# Buck_Boost.net
KiCad netlist of a schematic drawn in Altium Designer
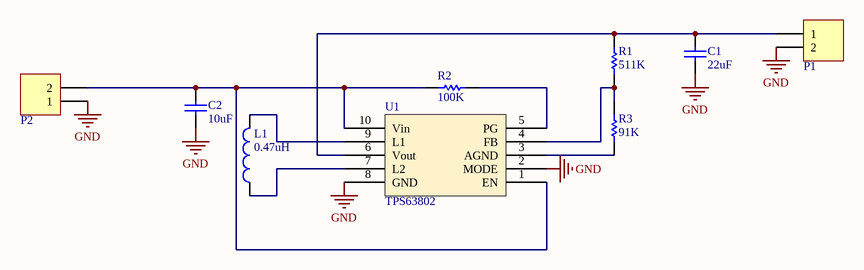
[diagram p0: Buck_Boost.SchDoc]

(export (version "E")
  (design (tool "Eeschema 10.0.6"))
  (components
    (comp (ref "C1")
      (value "22uF")
      (footprint "CAP-SM-0603")
      (description "Capacitor")
      (fields (field (name "Comment") "Cap Non-Pol SMD"))
      (libsource (lib "PIF_Library") (part "Cap Non-Pol SMD"))
    )
    (comp (ref "C2")
      (value "10uF")
      (footprint "CAP-SM-0603")
      (description "Capacitor")
      (fields (field (name "Comment") "Cap Non-Pol SMD"))
      (libsource (lib "PIF_Library") (part "Cap Non-Pol SMD"))
    )
    (comp (ref "L1")
      (value "0.47uH")
      (footprint "INDUCTOR 12.5x12.5")
      (description "Inductor")
      (libsource (lib "PIF_Library") (part "Inductor"))
    )
    (comp (ref "P1")
      (value "Domino 2")
      (footprint "DOMINO 2- 5mm")
      (description "Domino, 2-Pin")
      (fields (field (name "PUBLISHER") "Altium Limited"))
      (libsource (lib "") (part "Domino 2_1"))
    )
    (comp (ref "P2")
      (value "Domino 2")
      (footprint "DOMINO 2- 5mm")
      (description "Domino, 2-Pin")
      (fields (field (name "PUBLISHER") "Altium Limited"))
      (libsource (lib "PIF_Library") (part "Domino 2"))
    )
    (comp (ref "R1")
      (value "511K")
      (footprint "RES-SM-0603")
      (description "Resistor")
      (fields (field (name "Comment") "RESISTOR SMD"))
      (libsource (lib "PIF_Library") (part "RESISTOR SMD"))
    )
    (comp (ref "R2")
      (value "100K")
      (footprint "RES-SM-0603")
      (description "Resistor")
      (fields (field (name "Comment") "RESISTOR SMD"))
      (libsource (lib "PIF_Library") (part "RESISTOR SMD"))
    )
    (comp (ref "R3")
      (value "91K")
      (footprint "RES-SM-0603")
      (description "Resistor")
      (fields (field (name "Comment") "RESISTOR SMD"))
      (libsource (lib "PIF_Library") (part "RESISTOR SMD"))
    )
    (comp (ref "U1")
      (value "TPS63802")
      (footprint "TPS63802")
      (description "SMD")
      (libsource (lib "buck_boost") (part "TPS63802"))
    )
  )
  (nets
    (net (code "1") (name "GND") (class "Default")
      (node (ref "C1") (pin "2") (pinfunction "2_2") (pintype "passive"))
      (node (ref "C2") (pin "2") (pinfunction "2_2") (pintype "passive"))
      (node (ref "P1") (pin "2") (pinfunction "2_2") (pintype "passive"))
      (node (ref "P2") (pin "1") (pinfunction "1_1") (pintype "passive"))
      (node (ref "U1") (pin "2") (pinfunction "MODE_2") (pintype "passive"))
      (node (ref "U1") (pin "8") (pinfunction "GND_8") (pintype "passive"))
    )
    (net (code "2") (name "Net-(U1-AGND)") (class "Default")
      (node (ref "R3") (pin "1") (pinfunction "1_1") (pintype "passive"))
      (node (ref "U1") (pin "3") (pinfunction "AGND_3") (pintype "passive"))
    )
    (net (code "3") (name "Net-(U1-EN)") (class "Default")
      (node (ref "C2") (pin "1") (pinfunction "1_1") (pintype "passive"))
      (node (ref "P2") (pin "2") (pinfunction "2_2") (pintype "passive"))
      (node (ref "R2") (pin "1") (pinfunction "1_1") (pintype "passive"))
      (node (ref "U1") (pin "1") (pinfunction "EN_1") (pintype "passive"))
      (node (ref "U1") (pin "10") (pinfunction "Vin_10") (pintype "passive"))
    )
    (net (code "4") (name "Net-(U1-FB)") (class "Default")
      (node (ref "R1") (pin "1") (pinfunction "1_1") (pintype "passive"))
      (node (ref "R3") (pin "2") (pinfunction "2_2") (pintype "passive"))
      (node (ref "U1") (pin "4") (pinfunction "FB_4") (pintype "passive"))
    )
    (net (code "5") (name "Net-(U1-L1)") (class "Default")
      (node (ref "L1") (pin "2") (pinfunction "2_2") (pintype "passive"))
      (node (ref "U1") (pin "9") (pinfunction "L1_9") (pintype "passive"))
    )
    (net (code "6") (name "Net-(U1-L2)") (class "Default")
      (node (ref "L1") (pin "1") (pinfunction "1_1") (pintype "passive"))
      (node (ref "U1") (pin "7") (pinfunction "L2_7") (pintype "passive"))
    )
    (net (code "7") (name "Net-(U1-PG)") (class "Default")
      (node (ref "R2") (pin "2") (pinfunction "2_2") (pintype "passive"))
      (node (ref "U1") (pin "5") (pinfunction "PG_5") (pintype "passive"))
    )
    (net (code "8") (name "Net-(U1-Vout)") (class "Default")
      (node (ref "C1") (pin "1") (pinfunction "1_1") (pintype "passive"))
      (node (ref "P1") (pin "1") (pinfunction "1_1") (pintype "passive"))
      (node (ref "R1") (pin "2") (pinfunction "2_2") (pintype "passive"))
      (node (ref "U1") (pin "6") (pinfunction "Vout_6") (pintype "passive"))
    )
  )
)
